# ProProject__CW32__2024-01-24.net
KiCad netlist of a schematic drawn in EasyEDA Pro
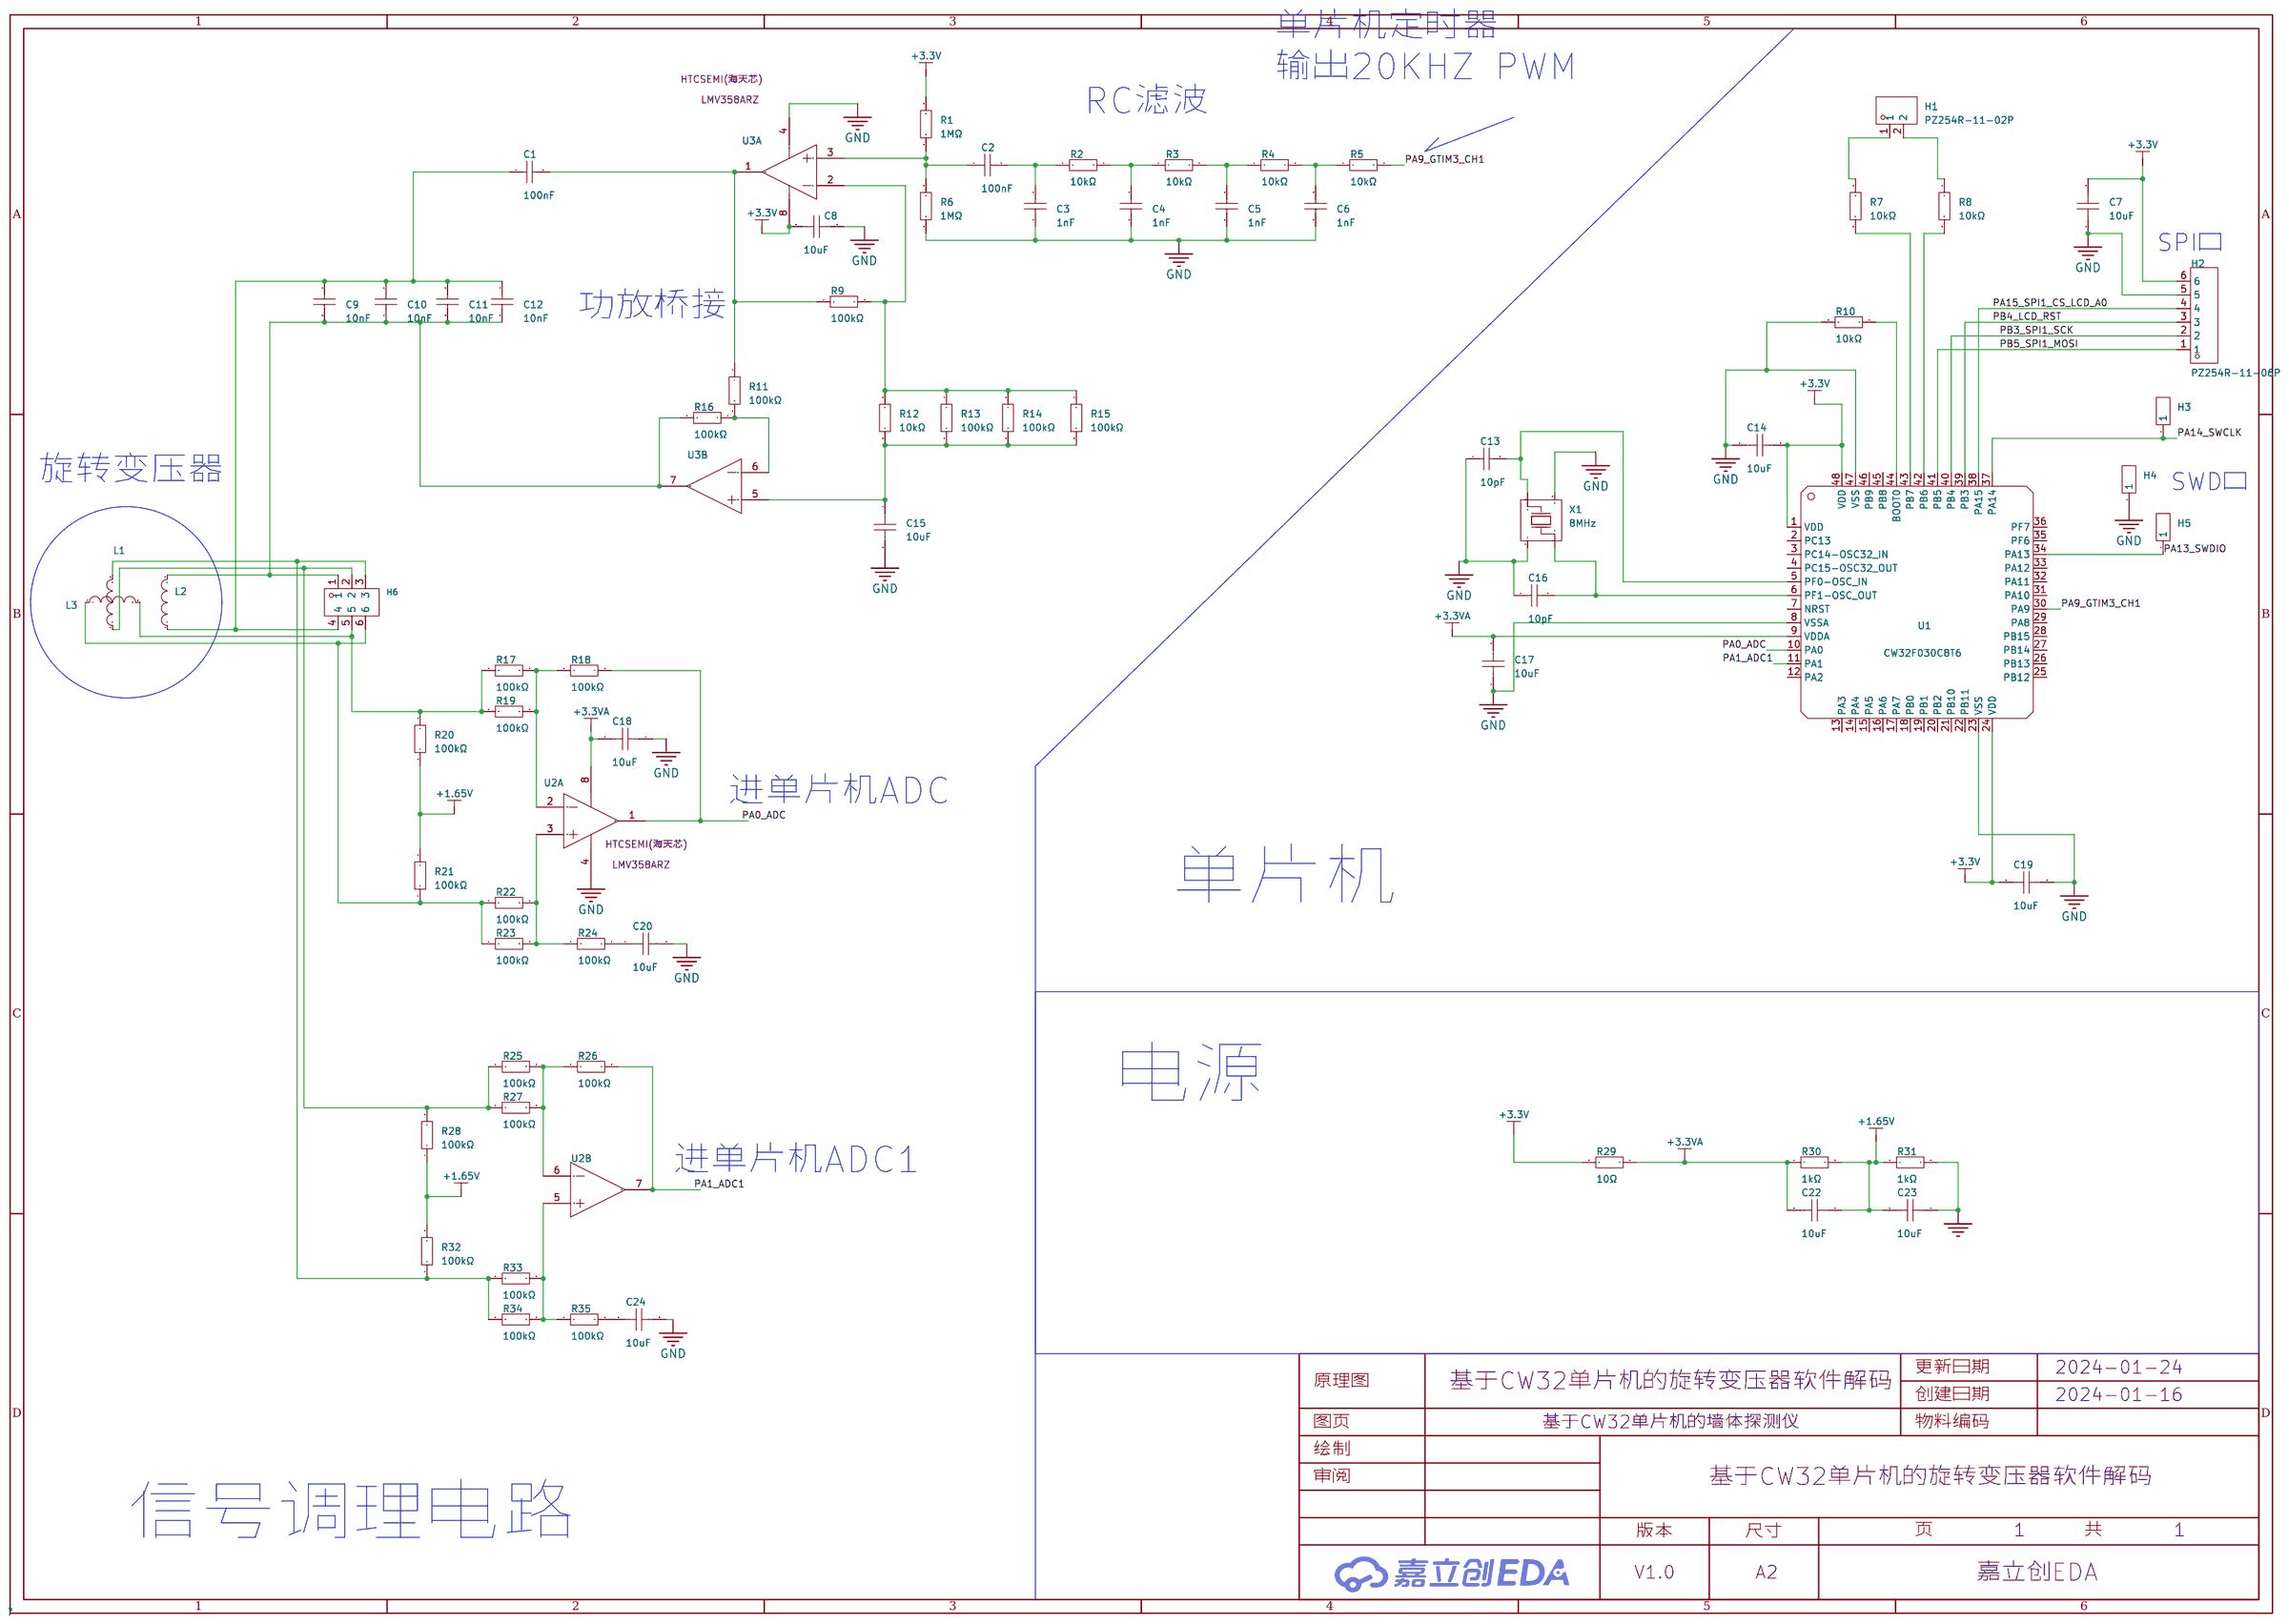
[diagram p0: schematic sheet]

(export (version "E")
  (design (tool "Eeschema 10.0.6"))
  (components
    (comp (ref "C1")
      (value "100nF")
      (footprint "easyedapro:C0603")
      (description "容值:100nF;精度:±10%;额定电压:50V;材质(温度系数):X7R;")
      (fields (field (name "Manufacturer Part") "0603B104K500NT") (field (name "Manufacturer") "FH(风华)"))
      (libsource (lib "easyedapro") (part "0603B104K500NT"))
    )
    (comp (ref "C2")
      (value "100nF")
      (footprint "easyedapro:C0603")
      (description "容值:100nF;精度:±10%;额定电压:50V;材质(温度系数):X7R;")
      (fields (field (name "Manufacturer Part") "0603B104K500NT") (field (name "Manufacturer") "FH(风华)"))
      (libsource (lib "easyedapro") (part "0603B104K500NT"))
    )
    (comp (ref "C3")
      (value "1nF")
      (footprint "easyedapro:C0603")
      (description "容值:1nF;精度:±5%;额定电压:50V;材质(温度系数):NP0;")
      (fields
        (field (name "Manufacturer Part") "CC0603JRNPO9BN102")
        (field (name "Manufacturer") "YAGEO(国巨)")
      )
      (libsource (lib "easyedapro") (part "CC0603JRNPO9BN102"))
    )
    (comp (ref "C4")
      (value "1nF")
      (footprint "easyedapro:C0603")
      (description "容值:1nF;精度:±5%;额定电压:50V;材质(温度系数):NP0;")
      (fields
        (field (name "Manufacturer Part") "CC0603JRNPO9BN102")
        (field (name "Manufacturer") "YAGEO(国巨)")
      )
      (libsource (lib "easyedapro") (part "CC0603JRNPO9BN102"))
    )
    (comp (ref "C5")
      (value "1nF")
      (footprint "easyedapro:C0603")
      (description "容值:1nF;精度:±5%;额定电压:50V;材质(温度系数):NP0;")
      (fields
        (field (name "Manufacturer Part") "CC0603JRNPO9BN102")
        (field (name "Manufacturer") "YAGEO(国巨)")
      )
      (libsource (lib "easyedapro") (part "CC0603JRNPO9BN102"))
    )
    (comp (ref "C6")
      (value "1nF")
      (footprint "easyedapro:C0603")
      (description "容值:1nF;精度:±5%;额定电压:50V;材质(温度系数):NP0;")
      (fields
        (field (name "Manufacturer Part") "CC0603JRNPO9BN102")
        (field (name "Manufacturer") "YAGEO(国巨)")
      )
      (libsource (lib "easyedapro") (part "CC0603JRNPO9BN102"))
    )
    (comp (ref "C7")
      (value "10uF")
      (footprint "easyedapro:C0603")
      (description "容值:10uF;精度:±10%;额定电压:10V;材质(温度系数):X5R;")
      (fields
        (field (name "Manufacturer Part") "CL10A106KP8NNNC")
        (field (name "Manufacturer") "SAMSUNG(三星)")
      )
      (libsource (lib "easyedapro") (part "CL10A106KP8NNNC"))
    )
    (comp (ref "C8")
      (value "10uF")
      (footprint "easyedapro:C0603")
      (description "容值:10uF;精度:±10%;额定电压:10V;材质(温度系数):X5R;")
      (fields
        (field (name "Manufacturer Part") "CL10A106KP8NNNC")
        (field (name "Manufacturer") "SAMSUNG(三星)")
      )
      (libsource (lib "easyedapro") (part "CL10A106KP8NNNC"))
    )
    (comp (ref "C9")
      (value "10nF")
      (footprint "easyedapro:C0603")
      (description "容值:10nF;精度:±10%;额定电压:50V;材质(温度系数):X7R;")
      (fields
        (field (name "Manufacturer Part") "CC0603KRX7R9BB103")
        (field (name "Manufacturer") "YAGEO(国巨)")
      )
      (libsource (lib "easyedapro") (part "CC0603KRX7R9BB103"))
    )
    (comp (ref "C10")
      (value "10nF")
      (footprint "easyedapro:C0603")
      (description "容值:10nF;精度:±10%;额定电压:50V;材质(温度系数):X7R;")
      (fields
        (field (name "Manufacturer Part") "CC0603KRX7R9BB103")
        (field (name "Manufacturer") "YAGEO(国巨)")
      )
      (libsource (lib "easyedapro") (part "CC0603KRX7R9BB103"))
    )
    (comp (ref "C11")
      (value "10nF")
      (footprint "easyedapro:C0603")
      (description "容值:10nF;精度:±10%;额定电压:50V;材质(温度系数):X7R;")
      (fields
        (field (name "Manufacturer Part") "CC0603KRX7R9BB103")
        (field (name "Manufacturer") "YAGEO(国巨)")
      )
      (libsource (lib "easyedapro") (part "CC0603KRX7R9BB103"))
    )
    (comp (ref "C12")
      (value "10nF")
      (footprint "easyedapro:C0603")
      (description "容值:10nF;精度:±10%;额定电压:50V;材质(温度系数):X7R;")
      (fields
        (field (name "Manufacturer Part") "CC0603KRX7R9BB103")
        (field (name "Manufacturer") "YAGEO(国巨)")
      )
      (libsource (lib "easyedapro") (part "CC0603KRX7R9BB103"))
    )
    (comp (ref "C13")
      (value "10pF")
      (footprint "easyedapro:C0603")
      (description "容值:10pF;精度:±5%;额定电压:50V;材质(温度系数):NP0;")
      (fields
        (field (name "Manufacturer Part") "CC0603JRNPO9BN100")
        (field (name "Manufacturer") "YAGEO(国巨)")
      )
      (libsource (lib "easyedapro") (part "CC0603JRNPO9BN100"))
    )
    (comp (ref "C14")
      (value "10uF")
      (footprint "easyedapro:C0603")
      (description "容值:10uF;精度:±10%;额定电压:10V;材质(温度系数):X5R;")
      (fields
        (field (name "Manufacturer Part") "CL10A106KP8NNNC")
        (field (name "Manufacturer") "SAMSUNG(三星)")
      )
      (libsource (lib "easyedapro") (part "CL10A106KP8NNNC"))
    )
    (comp (ref "C15")
      (value "10uF")
      (footprint "easyedapro:C0603")
      (description "容值:10uF;精度:±10%;额定电压:10V;材质(温度系数):X5R;")
      (fields
        (field (name "Manufacturer Part") "CL10A106KP8NNNC")
        (field (name "Manufacturer") "SAMSUNG(三星)")
      )
      (libsource (lib "easyedapro") (part "CL10A106KP8NNNC"))
    )
    (comp (ref "C16")
      (value "10pF")
      (footprint "easyedapro:C0603")
      (description "容值:10pF;精度:±5%;额定电压:50V;材质(温度系数):NP0;")
      (fields
        (field (name "Manufacturer Part") "CC0603JRNPO9BN100")
        (field (name "Manufacturer") "YAGEO(国巨)")
      )
      (libsource (lib "easyedapro") (part "CC0603JRNPO9BN100"))
    )
    (comp (ref "C17")
      (value "10uF")
      (footprint "easyedapro:C0603")
      (description "容值:10uF;精度:±10%;额定电压:10V;材质(温度系数):X5R;")
      (fields
        (field (name "Manufacturer Part") "CL10A106KP8NNNC")
        (field (name "Manufacturer") "SAMSUNG(三星)")
      )
      (libsource (lib "easyedapro") (part "CL10A106KP8NNNC"))
    )
    (comp (ref "C18")
      (value "10uF")
      (footprint "easyedapro:C0603")
      (description "容值:10uF;精度:±10%;额定电压:10V;材质(温度系数):X5R;")
      (fields
        (field (name "Manufacturer Part") "CL10A106KP8NNNC")
        (field (name "Manufacturer") "SAMSUNG(三星)")
      )
      (libsource (lib "easyedapro") (part "CL10A106KP8NNNC"))
    )
    (comp (ref "C19")
      (value "10uF")
      (footprint "easyedapro:C0603")
      (description "容值:10uF;精度:±10%;额定电压:10V;材质(温度系数):X5R;")
      (fields
        (field (name "Manufacturer Part") "CL10A106KP8NNNC")
        (field (name "Manufacturer") "SAMSUNG(三星)")
      )
      (libsource (lib "easyedapro") (part "CL10A106KP8NNNC"))
    )
    (comp (ref "C20")
      (value "10uF")
      (footprint "easyedapro:C0603")
      (description "容值:10uF;精度:±10%;额定电压:10V;材质(温度系数):X5R;")
      (fields
        (field (name "Manufacturer Part") "CL10A106KP8NNNC")
        (field (name "Manufacturer") "SAMSUNG(三星)")
      )
      (libsource (lib "easyedapro") (part "CL10A106KP8NNNC"))
    )
    (comp (ref "C22")
      (value "10uF")
      (footprint "easyedapro:C0603")
      (description "容值:10uF;精度:±10%;额定电压:10V;材质(温度系数):X5R;")
      (fields
        (field (name "Manufacturer Part") "CL10A106KP8NNNC")
        (field (name "Manufacturer") "SAMSUNG(三星)")
      )
      (libsource (lib "easyedapro") (part "CL10A106KP8NNNC"))
    )
    (comp (ref "C23")
      (value "10uF")
      (footprint "easyedapro:C0603")
      (description "容值:10uF;精度:±10%;额定电压:10V;材质(温度系数):X5R;")
      (fields
        (field (name "Manufacturer Part") "CL10A106KP8NNNC")
        (field (name "Manufacturer") "SAMSUNG(三星)")
      )
      (libsource (lib "easyedapro") (part "CL10A106KP8NNNC"))
    )
    (comp (ref "C24")
      (value "10uF")
      (footprint "easyedapro:C0603")
      (description "容值:10uF;精度:±10%;额定电压:10V;材质(温度系数):X5R;")
      (fields
        (field (name "Manufacturer Part") "CL10A106KP8NNNC")
        (field (name "Manufacturer") "SAMSUNG(三星)")
      )
      (libsource (lib "easyedapro") (part "CL10A106KP8NNNC"))
    )
    (comp (ref "H1")
      (value "PZ254R-11-02P")
      (footprint "easyedapro:HDR-TH_2P-P2.54-H-M-W10.4")
      (fields (field (name "Manufacturer") "XFCN(兴飞)"))
      (libsource (lib "easyedapro") (part "PZ254R-11-02P"))
    )
    (comp (ref "H2")
      (value "PZ254R-11-06P")
      (footprint "easyedapro:HDR-TH_6P-P2.54-H-M-W10.4")
      (fields (field (name "Manufacturer") "XFCN(兴飞)"))
      (libsource (lib "easyedapro") (part "PZ254R-11-06P"))
    )
    (comp (ref "H3")
      (value "~")
      (footprint "easyedapro:HDR-TH_1P-V-M_XKB_X4611WV-01I-C28D40")
      (libsource (lib "easyedapro") (part "HDR_1x1"))
    )
    (comp (ref "H4")
      (value "~")
      (footprint "easyedapro:HDR-TH_1P-V-M_XKB_X4611WV-01I-C28D40")
      (libsource (lib "easyedapro") (part "HDR_1x1"))
    )
    (comp (ref "H5")
      (value "~")
      (footprint "easyedapro:HDR-TH_1P-V-M_XKB_X4611WV-01I-C28D40")
      (libsource (lib "easyedapro") (part "HDR_1x1"))
    )
    (comp (ref "H6")
      (value "PZ254-2-03-Z-8.5")
      (footprint "easyedapro:HDR-TH_6P-P2.54-V-M-R2-C3-S2.54")
      (fields (field (name "Manufacturer") "HCTL(华灿天禄)"))
      (libsource (lib "easyedapro") (part "PZ254-2-03-Z-8.5"))
    )
    (comp (ref "L1")
      (value "10uH")
      (footprint "easyedapro:L1206")
      (libsource (lib "easyedapro") (part "CMI321609VR27KT"))
    )
    (comp (ref "L2")
      (value "6.3uH")
      (footprint "easyedapro:L1206")
      (libsource (lib "easyedapro") (part "CMI321609VR27KT"))
    )
    (comp (ref "L3")
      (value "10uH")
      (footprint "easyedapro:L1206")
      (libsource (lib "easyedapro") (part "CMI321609VR27KT"))
    )
    (comp (ref "R1")
      (value "1MΩ")
      (footprint "easyedapro:R0603")
      (description "电阻类型:厚膜电阻;阻值:1MΩ;精度:±1%;功率:100mW;")
      (fields
        (field (name "Manufacturer Part") "0603WAF1004T5E")
        (field (name "Manufacturer") "UNI-ROYAL(厚声)")
      )
      (libsource (lib "easyedapro") (part "0603WAF1004T5E"))
    )
    (comp (ref "R2")
      (value "10kΩ")
      (footprint "easyedapro:R0603")
      (description "电阻类型:厚膜电阻;阻值:10kΩ;精度:±1%;功率:100mW;")
      (fields (field (name "Manufacturer Part") "RC0603FR-0710KL") (field (name "Manufacturer") "YAGEO(国巨)"))
      (libsource (lib "easyedapro") (part "RC0603FR-0710KL"))
    )
    (comp (ref "R3")
      (value "10kΩ")
      (footprint "easyedapro:R0603")
      (description "电阻类型:厚膜电阻;阻值:10kΩ;精度:±1%;功率:100mW;")
      (fields (field (name "Manufacturer Part") "RC0603FR-0710KL") (field (name "Manufacturer") "YAGEO(国巨)"))
      (libsource (lib "easyedapro") (part "RC0603FR-0710KL"))
    )
    (comp (ref "R4")
      (value "10kΩ")
      (footprint "easyedapro:R0603")
      (description "电阻类型:厚膜电阻;阻值:10kΩ;精度:±1%;功率:100mW;")
      (fields (field (name "Manufacturer Part") "RC0603FR-0710KL") (field (name "Manufacturer") "YAGEO(国巨)"))
      (libsource (lib "easyedapro") (part "RC0603FR-0710KL"))
    )
    (comp (ref "R5")
      (value "10kΩ")
      (footprint "easyedapro:R0603")
      (description "电阻类型:厚膜电阻;阻值:10kΩ;精度:±1%;功率:100mW;")
      (fields (field (name "Manufacturer Part") "RC0603FR-0710KL") (field (name "Manufacturer") "YAGEO(国巨)"))
      (libsource (lib "easyedapro") (part "RC0603FR-0710KL"))
    )
    (comp (ref "R6")
      (value "1MΩ")
      (footprint "easyedapro:R0603")
      (description "电阻类型:厚膜电阻;阻值:1MΩ;精度:±1%;功率:100mW;")
      (fields
        (field (name "Manufacturer Part") "0603WAF1004T5E")
        (field (name "Manufacturer") "UNI-ROYAL(厚声)")
      )
      (libsource (lib "easyedapro") (part "0603WAF1004T5E"))
    )
    (comp (ref "R7")
      (value "10kΩ")
      (footprint "easyedapro:R0603")
      (description "电阻类型:厚膜电阻;阻值:10kΩ;精度:±1%;功率:100mW;")
      (fields (field (name "Manufacturer Part") "RC0603FR-0710KL") (field (name "Manufacturer") "YAGEO(国巨)"))
      (libsource (lib "easyedapro") (part "RC0603FR-0710KL"))
    )
    (comp (ref "R8")
      (value "10kΩ")
      (footprint "easyedapro:R0603")
      (description "电阻类型:厚膜电阻;阻值:10kΩ;精度:±1%;功率:100mW;")
      (fields (field (name "Manufacturer Part") "RC0603FR-0710KL") (field (name "Manufacturer") "YAGEO(国巨)"))
      (libsource (lib "easyedapro") (part "RC0603FR-0710KL"))
    )
    (comp (ref "R9")
      (value "100kΩ")
      (footprint "easyedapro:R0603")
      (description "电阻类型:厚膜电阻;阻值:100kΩ;精度:±1%;功率:100mW;")
      (fields (field (name "Manufacturer Part") "RC0603FR-07100KL") (field (name "Manufacturer") "YAGEO(国巨)"))
      (libsource (lib "easyedapro") (part "RC0603FR-07100KL"))
    )
    (comp (ref "R10")
      (value "10kΩ")
      (footprint "easyedapro:R0603")
      (description "电阻类型:厚膜电阻;阻值:10kΩ;精度:±1%;功率:100mW;")
      (fields (field (name "Manufacturer Part") "RC0603FR-0710KL") (field (name "Manufacturer") "YAGEO(国巨)"))
      (libsource (lib "easyedapro") (part "RC0603FR-0710KL"))
    )
    (comp (ref "R11")
      (value "100kΩ")
      (footprint "easyedapro:R0603")
      (description "电阻类型:厚膜电阻;阻值:100kΩ;精度:±1%;功率:100mW;")
      (fields (field (name "Manufacturer Part") "RC0603FR-07100KL") (field (name "Manufacturer") "YAGEO(国巨)"))
      (libsource (lib "easyedapro") (part "RC0603FR-07100KL"))
    )
    (comp (ref "R12")
      (value "10kΩ")
      (footprint "easyedapro:R0603")
      (description "电阻类型:厚膜电阻;阻值:10kΩ;精度:±1%;功率:100mW;")
      (fields (field (name "Manufacturer Part") "RC0603FR-0710KL") (field (name "Manufacturer") "YAGEO(国巨)"))
      (libsource (lib "easyedapro") (part "RC0603FR-0710KL"))
    )
    (comp (ref "R13")
      (value "100kΩ")
      (footprint "easyedapro:R0603")
      (description "电阻类型:厚膜电阻;阻值:100kΩ;精度:±1%;功率:100mW;")
      (fields (field (name "Manufacturer Part") "RC0603FR-07100KL") (field (name "Manufacturer") "YAGEO(国巨)"))
      (libsource (lib "easyedapro") (part "RC0603FR-07100KL"))
    )
    (comp (ref "R14")
      (value "100kΩ")
      (footprint "easyedapro:R0603")
      (description "电阻类型:厚膜电阻;阻值:100kΩ;精度:±1%;功率:100mW;")
      (fields (field (name "Manufacturer Part") "RC0603FR-07100KL") (field (name "Manufacturer") "YAGEO(国巨)"))
      (libsource (lib "easyedapro") (part "RC0603FR-07100KL"))
    )
    (comp (ref "R15")
      (value "100kΩ")
      (footprint "easyedapro:R0603")
      (description "电阻类型:厚膜电阻;阻值:100kΩ;精度:±1%;功率:100mW;")
      (fields (field (name "Manufacturer Part") "RC0603FR-07100KL") (field (name "Manufacturer") "YAGEO(国巨)"))
      (libsource (lib "easyedapro") (part "RC0603FR-07100KL"))
    )
    (comp (ref "R16")
      (value "100kΩ")
      (footprint "easyedapro:R0603")
      (description "电阻类型:厚膜电阻;阻值:100kΩ;精度:±1%;功率:100mW;")
      (fields (field (name "Manufacturer Part") "RC0603FR-07100KL") (field (name "Manufacturer") "YAGEO(国巨)"))
      (libsource (lib "easyedapro") (part "RC0603FR-07100KL"))
    )
    (comp (ref "R17")
      (value "100kΩ")
      (footprint "easyedapro:R0603")
      (description "电阻类型:厚膜电阻;阻值:100kΩ;精度:±1%;功率:100mW;")
      (fields (field (name "Manufacturer Part") "RC0603FR-07100KL") (field (name "Manufacturer") "YAGEO(国巨)"))
      (libsource (lib "easyedapro") (part "RC0603FR-07100KL"))
    )
    (comp (ref "R18")
      (value "100kΩ")
      (footprint "easyedapro:R0603")
      (description "电阻类型:厚膜电阻;阻值:100kΩ;精度:±1%;功率:100mW;")
      (fields (field (name "Manufacturer Part") "RC0603FR-07100KL") (field (name "Manufacturer") "YAGEO(国巨)"))
      (libsource (lib "easyedapro") (part "RC0603FR-07100KL"))
    )
    (comp (ref "R19")
      (value "100kΩ")
      (footprint "easyedapro:R0603")
      (description "电阻类型:厚膜电阻;阻值:100kΩ;精度:±1%;功率:100mW;")
      (fields (field (name "Manufacturer Part") "RC0603FR-07100KL") (field (name "Manufacturer") "YAGEO(国巨)"))
      (libsource (lib "easyedapro") (part "RC0603FR-07100KL"))
    )
    (comp (ref "R20")
      (value "100kΩ")
      (footprint "easyedapro:R0603")
      (description "电阻类型:厚膜电阻;阻值:100kΩ;精度:±1%;功率:100mW;")
      (fields (field (name "Manufacturer Part") "RC0603FR-07100KL") (field (name "Manufacturer") "YAGEO(国巨)"))
      (libsource (lib "easyedapro") (part "RC0603FR-07100KL"))
    )
    (comp (ref "R21")
      (value "100kΩ")
      (footprint "easyedapro:R0603")
      (description "电阻类型:厚膜电阻;阻值:100kΩ;精度:±1%;功率:100mW;")
      (fields (field (name "Manufacturer Part") "RC0603FR-07100KL") (field (name "Manufacturer") "YAGEO(国巨)"))
      (libsource (lib "easyedapro") (part "RC0603FR-07100KL"))
    )
    (comp (ref "R22")
      (value "100kΩ")
      (footprint "easyedapro:R0603")
      (description "电阻类型:厚膜电阻;阻值:100kΩ;精度:±1%;功率:100mW;")
      (fields (field (name "Manufacturer Part") "RC0603FR-07100KL") (field (name "Manufacturer") "YAGEO(国巨)"))
      (libsource (lib "easyedapro") (part "RC0603FR-07100KL"))
    )
    (comp (ref "R23")
      (value "100kΩ")
      (footprint "easyedapro:R0603")
      (description "电阻类型:厚膜电阻;阻值:100kΩ;精度:±1%;功率:100mW;")
      (fields (field (name "Manufacturer Part") "RC0603FR-07100KL") (field (name "Manufacturer") "YAGEO(国巨)"))
      (libsource (lib "easyedapro") (part "RC0603FR-07100KL"))
    )
    (comp (ref "R24")
      (value "100kΩ")
      (footprint "easyedapro:R0603")
      (description "电阻类型:厚膜电阻;阻值:100kΩ;精度:±1%;功率:100mW;")
      (fields (field (name "Manufacturer Part") "RC0603FR-07100KL") (field (name "Manufacturer") "YAGEO(国巨)"))
      (libsource (lib "easyedapro") (part "RC0603FR-07100KL"))
    )
    (comp (ref "R25")
      (value "100kΩ")
      (footprint "easyedapro:R0603")
      (description "电阻类型:厚膜电阻;阻值:100kΩ;精度:±1%;功率:100mW;")
      (fields (field (name "Manufacturer Part") "RC0603FR-07100KL") (field (name "Manufacturer") "YAGEO(国巨)"))
      (libsource (lib "easyedapro") (part "RC0603FR-07100KL"))
    )
    (comp (ref "R26")
      (value "100kΩ")
      (footprint "easyedapro:R0603")
      (description "电阻类型:厚膜电阻;阻值:100kΩ;精度:±1%;功率:100mW;")
      (fields (field (name "Manufacturer Part") "RC0603FR-07100KL") (field (name "Manufacturer") "YAGEO(国巨)"))
      (libsource (lib "easyedapro") (part "RC0603FR-07100KL"))
    )
    (comp (ref "R27")
      (value "100kΩ")
      (footprint "easyedapro:R0603")
      (description "电阻类型:厚膜电阻;阻值:100kΩ;精度:±1%;功率:100mW;")
      (fields (field (name "Manufacturer Part") "RC0603FR-07100KL") (field (name "Manufacturer") "YAGEO(国巨)"))
      (libsource (lib "easyedapro") (part "RC0603FR-07100KL"))
    )
    (comp (ref "R28")
      (value "100kΩ")
      (footprint "easyedapro:R0603")
      (description "电阻类型:厚膜电阻;阻值:100kΩ;精度:±1%;功率:100mW;")
      (fields (field (name "Manufacturer Part") "RC0603FR-07100KL") (field (name "Manufacturer") "YAGEO(国巨)"))
      (libsource (lib "easyedapro") (part "RC0603FR-07100KL"))
    )
    (comp (ref "R29")
      (value "10Ω")
      (footprint "easyedapro:R0603")
      (description "电阻类型:厚膜电阻;阻值:10Ω;精度:±1%;功率:100mW;")
      (fields
        (field (name "Manufacturer Part") "0603WAF100JT5E")
        (field (name "Manufacturer") "UNI-ROYAL(厚声)")
      )
      (libsource (lib "easyedapro") (part "0603WAF100JT5E"))
    )
    (comp (ref "R30")
      (value "1kΩ")
      (footprint "easyedapro:R0603")
      (description "电阻类型:厚膜电阻;阻值:1kΩ;精度:±1%;功率:100mW;")
      (fields (field (name "Manufacturer Part") "RC0603FR-071KL") (field (name "Manufacturer") "YAGEO(国巨)"))
      (libsource (lib "easyedapro") (part "RC0603FR-071KL"))
    )
    (comp (ref "R31")
      (value "1kΩ")
      (footprint "easyedapro:R0603")
      (description "电阻类型:厚膜电阻;阻值:1kΩ;精度:±1%;功率:100mW;")
      (fields (field (name "Manufacturer Part") "RC0603FR-071KL") (field (name "Manufacturer") "YAGEO(国巨)"))
      (libsource (lib "easyedapro") (part "RC0603FR-071KL"))
    )
    (comp (ref "R32")
      (value "100kΩ")
      (footprint "easyedapro:R0603")
      (description "电阻类型:厚膜电阻;阻值:100kΩ;精度:±1%;功率:100mW;")
      (fields (field (name "Manufacturer Part") "RC0603FR-07100KL") (field (name "Manufacturer") "YAGEO(国巨)"))
      (libsource (lib "easyedapro") (part "RC0603FR-07100KL"))
    )
    (comp (ref "R33")
      (value "100kΩ")
      (footprint "easyedapro:R0603")
      (description "电阻类型:厚膜电阻;阻值:100kΩ;精度:±1%;功率:100mW;")
      (fields (field (name "Manufacturer Part") "RC0603FR-07100KL") (field (name "Manufacturer") "YAGEO(国巨)"))
      (libsource (lib "easyedapro") (part "RC0603FR-07100KL"))
    )
    (comp (ref "R34")
      (value "100kΩ")
      (footprint "easyedapro:R0603")
      (description "电阻类型:厚膜电阻;阻值:100kΩ;精度:±1%;功率:100mW;")
      (fields (field (name "Manufacturer Part") "RC0603FR-07100KL") (field (name "Manufacturer") "YAGEO(国巨)"))
      (libsource (lib "easyedapro") (part "RC0603FR-07100KL"))
    )
    (comp (ref "R35")
      (value "100kΩ")
      (footprint "easyedapro:R0603")
      (description "电阻类型:厚膜电阻;阻值:100kΩ;精度:±1%;功率:100mW;")
      (fields (field (name "Manufacturer Part") "RC0603FR-07100KL") (field (name "Manufacturer") "YAGEO(国巨)"))
      (libsource (lib "easyedapro") (part "RC0603FR-07100KL"))
    )
    (comp (ref "U1")
      (value "CW32F030C8T6")
      (footprint "easyedapro:LQFP-48_L7.0-W7.0-P0.50-LS9.0-TL")
      (fields (field (name "Manufacturer") "CW(芯源)"))
      (libsource (lib "easyedapro") (part "CW32F030C8T6_C3019113"))
    )
    (comp (ref "U2")
      (value "{ManufacturerPart!}")
      (footprint "easyedapro:SOP-8_L4.9-W3.9-P1.27-LS6.0-BL")
      (description "CMOS低功耗双路运算放大器")
      (fields (field (name "Manufacturer Part") "LMV358ARZ") (field (name "Manufacturer") "HTCSEMI(海天芯)"))
      (libsource (lib "easyedapro") (part "LMV358ARZ"))
    )
    (comp (ref "U3")
      (value "{ManufacturerPart!}")
      (footprint "easyedapro:SOP-8_L4.9-W3.9-P1.27-LS6.0-BL")
      (description "CMOS低功耗双路运算放大器")
      (fields (field (name "Manufacturer Part") "LMV358ARZ") (field (name "Manufacturer") "HTCSEMI(海天芯)"))
      (libsource (lib "easyedapro") (part "LMV358ARZ"))
    )
    (comp (ref "X1")
      (value "8MHz")
      (footprint "easyedapro:OSC-SMD_4P-L3.2-W2.5-BL")
      (description "频率:8MHz;负载电容:10pF;频率公差:±10ppm;")
      (fields (field (name "Manufacturer Part") "TAXM8M4RDBCCT2T") (field (name "Manufacturer") "YJX(雅晶鑫)"))
      (libsource (lib "easyedapro") (part "TAXM8M4RDBCCT2T"))
    )
  )
  (nets
    (net (code "1") (name "+1.65V") (class "Default")
      (node (ref "C22") (pin "1") (pinfunction "1_1") (pintype "unspecified"))
      (node (ref "C23") (pin "2") (pinfunction "2_2") (pintype "unspecified"))
      (node (ref "R20") (pin "1") (pinfunction "1_1") (pintype "unspecified"))
      (node (ref "R21") (pin "2") (pinfunction "2_2") (pintype "unspecified"))
      (node (ref "R28") (pin "1") (pinfunction "1_1") (pintype "unspecified"))
      (node (ref "R30") (pin "2") (pinfunction "2_2") (pintype "input"))
      (node (ref "R31") (pin "1") (pinfunction "1_1") (pintype "input"))
      (node (ref "R32") (pin "2") (pinfunction "2_2") (pintype "unspecified"))
    )
    (net (code "2") (name "+3.3V") (class "Default")
      (node (ref "C14") (pin "2") (pinfunction "2_2") (pintype "unspecified"))
      (node (ref "C19") (pin "1") (pinfunction "1_1") (pintype "unspecified"))
      (node (ref "C7") (pin "2") (pinfunction "2_2") (pintype "unspecified"))
      (node (ref "C8") (pin "2") (pinfunction "2_2") (pintype "unspecified"))
      (node (ref "H2") (pin "6") (pinfunction "6_6") (pintype "unspecified"))
      (node (ref "R1") (pin "2") (pinfunction "2_2") (pintype "input"))
      (node (ref "R29") (pin "2") (pinfunction "2_2") (pintype "input"))
      (node (ref "U1") (pin "1") (pinfunction "VDD_1") (pintype "input"))
      (node (ref "U1") (pin "24") (pinfunction "VDD_24") (pintype "input"))
      (node (ref "U1") (pin "48") (pinfunction "VDD_48") (pintype "input"))
      (node (ref "U3") (pin "8") (pinfunction "VCC_8") (pintype "input"))
    )
    (net (code "3") (name "+3.3VA") (class "Default")
      (node (ref "C17") (pin "2") (pinfunction "2_2") (pintype "unspecified"))
      (node (ref "C18") (pin "2") (pinfunction "2_2") (pintype "unspecified"))
      (node (ref "C22") (pin "2") (pinfunction "2_2") (pintype "unspecified"))
      (node (ref "R29") (pin "1") (pinfunction "1_1") (pintype "input"))
      (node (ref "R30") (pin "1") (pinfunction "1_1") (pintype "input"))
      (node (ref "U1") (pin "9") (pinfunction "VDDA_9") (pintype "input"))
      (node (ref "U2") (pin "8") (pinfunction "VCC_8") (pintype "input"))
    )
    (net (code "4") (name "/PA0_ADC") (class "Default")
      (node (ref "R18") (pin "2") (pinfunction "2_2") (pintype "unspecified"))
      (node (ref "U1") (pin "10") (pinfunction "PA0_10") (pintype "input"))
      (node (ref "U2") (pin "1") (pinfunction "OUT_1") (pintype "output"))
    )
    (net (code "5") (name "/PA1_ADC1") (class "Default")
      (node (ref "R26") (pin "2") (pinfunction "2_2") (pintype "unspecified"))
      (node (ref "U1") (pin "11") (pinfunction "PA1_11") (pintype "input"))
      (node (ref "U2") (pin "7") (pinfunction "OUT2_7") (pintype "output"))
    )
    (net (code "6") (name "/PA9_GTIM3_CH1") (class "Default")
      (node (ref "R5") (pin "2") (pinfunction "2_2") (pintype "input"))
      (node (ref "U1") (pin "30") (pinfunction "PA9_30") (pintype "input"))
    )
    (net (code "7") (name "/PA13_SWDIO") (class "Default")
      (node (ref "H5") (pin "1") (pinfunction "1_1") (pintype "unspecified"))
      (node (ref "U1") (pin "34") (pinfunction "PA13_34") (pintype "input"))
    )
    (net (code "8") (name "/PA14_SWCLK") (class "Default")
      (node (ref "H3") (pin "1") (pinfunction "1_1") (pintype "unspecified"))
      (node (ref "U1") (pin "37") (pinfunction "PA14_37") (pintype "input"))
    )
    (net (code "9") (name "/PA15_SPI1_CS_LCD_A0") (class "Default")
      (node (ref "H2") (pin "4") (pinfunction "4_4") (pintype "unspecified"))
      (node (ref "U1") (pin "38") (pinfunction "PA15_38") (pintype "input"))
    )
    (net (code "10") (name "/PB3_SPI1_SCK") (class "Default")
      (node (ref "H2") (pin "2") (pinfunction "2_2") (pintype "unspecified"))
      (node (ref "U1") (pin "40") (pinfunction "PB4_40") (pintype "input"))
    )
    (net (code "11") (name "/PB4_LCD_RST") (class "Default")
      (node (ref "H2") (pin "3") (pinfunction "3_3") (pintype "unspecified"))
      (node (ref "U1") (pin "39") (pinfunction "PB3_39") (pintype "input"))
    )
    (net (code "12") (name "/PB5_SPI1_MOSI") (class "Default")
      (node (ref "H2") (pin "1") (pinfunction "1_1") (pintype "unspecified"))
      (node (ref "U1") (pin "41") (pinfunction "PB5_41") (pintype "input"))
    )
    (net (code "13") (name "GND") (class "Default")
      (node (ref "C13") (pin "1") (pinfunction "1_1") (pintype "input"))
      (node (ref "C14") (pin "1") (pinfunction "1_1") (pintype "unspecified"))
      (node (ref "C15") (pin "2") (pinfunction "2_2") (pintype "unspecified"))
      (node (ref "C16") (pin "1") (pinfunction "1_1") (pintype "input"))
      (node (ref "C17") (pin "1") (pinfunction "1_1") (pintype "unspecified"))
      (node (ref "C18") (pin "1") (pinfunction "1_1") (pintype "unspecified"))
      (node (ref "C19") (pin "2") (pinfunction "2_2") (pintype "unspecified"))
      (node (ref "C20") (pin "2") (pinfunction "2_2") (pintype "unspecified"))
      (node (ref "C23") (pin "1") (pinfunction "1_1") (pintype "unspecified"))
      (node (ref "C24") (pin "2") (pinfunction "2_2") (pintype "unspecified"))
      (node (ref "C3") (pin "1") (pinfunction "1_1") (pintype "input"))
      (node (ref "C4") (pin "1") (pinfunction "1_1") (pintype "input"))
      (node (ref "C5") (pin "1") (pinfunction "1_1") (pintype "input"))
      (node (ref "C6") (pin "1") (pinfunction "1_1") (pintype "input"))
      (node (ref "C7") (pin "1") (pinfunction "1_1") (pintype "unspecified"))
      (node (ref "C8") (pin "1") (pinfunction "1_1") (pintype "unspecified"))
      (node (ref "H2") (pin "5") (pinfunction "5_5") (pintype "unspecified"))
      (node (ref "H4") (pin "1") (pinfunction "1_1") (pintype "unspecified"))
      (node (ref "R10") (pin "2") (pinfunction "2_2") (pintype "input"))
      (node (ref "R31") (pin "2") (pinfunction "2_2") (pintype "input"))
      (node (ref "R6") (pin "1") (pinfunction "1_1") (pintype "input"))
      (node (ref "U1") (pin "23") (pinfunction "VSS_23") (pintype "input"))
      (node (ref "U1") (pin "47") (pinfunction "VSS_47") (pintype "input"))
      (node (ref "U1") (pin "8") (pinfunction "VSSA_8") (pintype "input"))
      (node (ref "U2") (pin "4") (pinfunction "GND_4") (pintype "input"))
      (node (ref "U3") (pin "4") (pinfunction "GND_4") (pintype "input"))
      (node (ref "X1") (pin "2") (pinfunction "2_2") (pintype "input"))
      (node (ref "X1") (pin "4") (pinfunction "4_4") (pintype "input"))
    )
    (net (code "14") (name "Net-(C1-Pad1)") (class "Default")
      (node (ref "C1") (pin "1") (pinfunction "1_1") (pintype "input"))
      (node (ref "C10") (pin "2") (pinfunction "2_2") (pintype "input"))
      (node (ref "C11") (pin "2") (pinfunction "2_2") (pintype "input"))
      (node (ref "C12") (pin "2") (pinfunction "2_2") (pintype "input"))
      (node (ref "C9") (pin "2") (pinfunction "2_2") (pintype "input"))
      (node (ref "H6") (pin "4") (pinfunction "4_4") (pintype "input"))
      (node (ref "L2") (pin "1") (pinfunction "1_1") (pintype "input"))
    )
    (net (code "15") (name "Net-(C2-Pad2)") (class "Default")
      (node (ref "C2") (pin "2") (pinfunction "2_2") (pintype "input"))
      (node (ref "C3") (pin "2") (pinfunction "2_2") (pintype "input"))
      (node (ref "R2") (pin "1") (pinfunction "1_1") (pintype "input"))
    )
    (net (code "16") (name "Net-(C4-Pad2)") (class "Default")
      (node (ref "C4") (pin "2") (pinfunction "2_2") (pintype "input"))
      (node (ref "R2") (pin "2") (pinfunction "2_2") (pintype "input"))
      (node (ref "R3") (pin "1") (pinfunction "1_1") (pintype "input"))
    )
    (net (code "17") (name "Net-(C5-Pad2)") (class "Default")
      (node (ref "C5") (pin "2") (pinfunction "2_2") (pintype "input"))
      (node (ref "R3") (pin "2") (pinfunction "2_2") (pintype "input"))
      (node (ref "R4") (pin "1") (pinfunction "1_1") (pintype "input"))
    )
    (net (code "18") (name "Net-(C6-Pad2)") (class "Default")
      (node (ref "C6") (pin "2") (pinfunction "2_2") (pintype "input"))
      (node (ref "R4") (pin "2") (pinfunction "2_2") (pintype "input"))
      (node (ref "R5") (pin "1") (pinfunction "1_1") (pintype "input"))
    )
    (net (code "19") (name "Net-(C20-Pad1)") (class "Default")
      (node (ref "C20") (pin "1") (pinfunction "1_1") (pintype "unspecified"))
      (node (ref "R24") (pin "2") (pinfunction "2_2") (pintype "unspecified"))
    )
    (net (code "20") (name "Net-(C24-Pad1)") (class "Default")
      (node (ref "C24") (pin "1") (pinfunction "1_1") (pintype "unspecified"))
      (node (ref "R35") (pin "2") (pinfunction "2_2") (pintype "unspecified"))
    )
    (net (code "21") (name "Net-(H1-Pad1)") (class "Default")
      (node (ref "H1") (pin "1") (pinfunction "1_1") (pintype "unspecified"))
      (node (ref "R7") (pin "1") (pinfunction "1_1") (pintype "input"))
    )
    (net (code "22") (name "Net-(H1-Pad2)") (class "Default")
      (node (ref "H1") (pin "2") (pinfunction "2_2") (pintype "unspecified"))
      (node (ref "R8") (pin "1") (pinfunction "1_1") (pintype "input"))
    )
    (net (code "23") (name "Net-(H6-Pad2)") (class "Default")
      (node (ref "H6") (pin "2") (pinfunction "2_2") (pintype "input"))
      (node (ref "L1") (pin "1") (pinfunction "1_1") (pintype "input"))
      (node (ref "R25") (pin "1") (pinfunction "1_1") (pintype "unspecified"))
      (node (ref "R27") (pin "1") (pinfunction "1_1") (pintype "unspecified"))
      (node (ref "R28") (pin "2") (pinfunction "2_2") (pintype "unspecified"))
    )
    (net (code "24") (name "Net-(H6-Pad3)") (class "Default")
      (node (ref "H6") (pin "3") (pinfunction "3_3") (pintype "input"))
      (node (ref "L1") (pin "2") (pinfunction "2_2") (pintype "input"))
      (node (ref "R32") (pin "1") (pinfunction "1_1") (pintype "unspecified"))
      (node (ref "R33") (pin "1") (pinfunction "1_1") (pintype "unspecified"))
      (node (ref "R34") (pin "1") (pinfunction "1_1") (pintype "unspecified"))
    )
    (net (code "25") (name "Net-(H6-Pad5)") (class "Default")
      (node (ref "H6") (pin "5") (pinfunction "5_5") (pintype "input"))
      (node (ref "L3") (pin "2") (pinfunction "2_2") (pintype "input"))
      (node (ref "R17") (pin "1") (pinfunction "1_1") (pintype "unspecified"))
      (node (ref "R19") (pin "1") (pinfunction "1_1") (pintype "unspecified"))
      (node (ref "R20") (pin "2") (pinfunction "2_2") (pintype "unspecified"))
    )
    (net (code "26") (name "Net-(H6-Pad6)") (class "Default")
      (node (ref "H6") (pin "6") (pinfunction "6_6") (pintype "input"))
      (node (ref "L3") (pin "1") (pinfunction "1_1") (pintype "input"))
      (node (ref "R21") (pin "1") (pinfunction "1_1") (pintype "unspecified"))
      (node (ref "R22") (pin "1") (pinfunction "1_1") (pintype "unspecified"))
      (node (ref "R23") (pin "1") (pinfunction "1_1") (pintype "unspecified"))
    )
    (net (code "27") (name "Net-(U1-BOOT0)") (class "Default")
      (node (ref "R10") (pin "1") (pinfunction "1_1") (pintype "input"))
      (node (ref "U1") (pin "44") (pinfunction "BOOT0_44") (pintype "input"))
    )
    (net (code "28") (name "Net-(U1-PB6)") (class "Default")
      (node (ref "R8") (pin "2") (pinfunction "2_2") (pintype "input"))
      (node (ref "U1") (pin "42") (pinfunction "PB6_42") (pintype "input"))
    )
    (net (code "29") (name "Net-(U1-PB7)") (class "Default")
      (node (ref "R7") (pin "2") (pinfunction "2_2") (pintype "input"))
      (node (ref "U1") (pin "43") (pinfunction "PB7_43") (pintype "input"))
    )
    (net (code "30") (name "Net-(U1-PF0-OSC_IN)") (class "Default")
      (node (ref "C13") (pin "2") (pinfunction "2_2") (pintype "input"))
      (node (ref "U1") (pin "5") (pinfunction "PF0-OSC_IN_5") (pintype "input"))
      (node (ref "X1") (pin "3") (pinfunction "3_3") (pintype "input"))
    )
    (net (code "31") (name "Net-(U1-PF1-OSC_OUT)") (class "Default")
      (node (ref "C16") (pin "2") (pinfunction "2_2") (pintype "input"))
      (node (ref "U1") (pin "6") (pinfunction "PF1-OSC_OUT_6") (pintype "input"))
      (node (ref "X1") (pin "1") (pinfunction "1_1") (pintype "input"))
    )
    (net (code "32") (name "Net-(U2A-IN1+)") (class "Default")
      (node (ref "R22") (pin "2") (pinfunction "2_2") (pintype "unspecified"))
      (node (ref "R23") (pin "2") (pinfunction "2_2") (pintype "unspecified"))
      (node (ref "R24") (pin "1") (pinfunction "1_1") (pintype "unspecified"))
      (node (ref "U2") (pin "3") (pinfunction "IN1+_3") (pintype "input"))
    )
    (net (code "33") (name "Net-(U2A-IN1-)") (class "Default")
      (node (ref "R17") (pin "2") (pinfunction "2_2") (pintype "unspecified"))
      (node (ref "R18") (pin "1") (pinfunction "1_1") (pintype "unspecified"))
      (node (ref "R19") (pin "2") (pinfunction "2_2") (pintype "unspecified"))
      (node (ref "U2") (pin "2") (pinfunction "IN1-_2") (pintype "input"))
    )
    (net (code "34") (name "Net-(U2B-IN2+)") (class "Default")
      (node (ref "R33") (pin "2") (pinfunction "2_2") (pintype "unspecified"))
      (node (ref "R34") (pin "2") (pinfunction "2_2") (pintype "unspecified"))
      (node (ref "R35") (pin "1") (pinfunction "1_1") (pintype "unspecified"))
      (node (ref "U2") (pin "5") (pinfunction "IN2+_5") (pintype "input"))
    )
    (net (code "35") (name "Net-(U2B-IN2-)") (class "Default")
      (node (ref "R25") (pin "2") (pinfunction "2_2") (pintype "unspecified"))
      (node (ref "R26") (pin "1") (pinfunction "1_1") (pintype "unspecified"))
      (node (ref "R27") (pin "2") (pinfunction "2_2") (pintype "unspecified"))
      (node (ref "U2") (pin "6") (pinfunction "IN2-_6") (pintype "input"))
    )
    (net (code "36") (name "Net-(U3A-IN1+)") (class "Default")
      (node (ref "C2") (pin "1") (pinfunction "1_1") (pintype "input"))
      (node (ref "R1") (pin "1") (pinfunction "1_1") (pintype "input"))
      (node (ref "R6") (pin "2") (pinfunction "2_2") (pintype "input"))
      (node (ref "U3") (pin "3") (pinfunction "IN1+_3") (pintype "input"))
    )
    (net (code "37") (name "Net-(U3A-IN1-)") (class "Default")
      (node (ref "R12") (pin "2") (pinfunction "2_2") (pintype "input"))
      (node (ref "R13") (pin "1") (pinfunction "1_1") (pintype "unspecified"))
      (node (ref "R14") (pin "1") (pinfunction "1_1") (pintype "unspecified"))
      (node (ref "R15") (pin "1") (pinfunction "1_1") (pintype "unspecified"))
      (node (ref "R9") (pin "2") (pinfunction "2_2") (pintype "unspecified"))
      (node (ref "U3") (pin "2") (pinfunction "IN1-_2") (pintype "input"))
    )
    (net (code "38") (name "Net-(U3A-OUT)") (class "Default")
      (node (ref "C1") (pin "2") (pinfunction "2_2") (pintype "input"))
      (node (ref "R11") (pin "1") (pinfunction "1_1") (pintype "unspecified"))
      (node (ref "R9") (pin "1") (pinfunction "1_1") (pintype "unspecified"))
      (node (ref "U3") (pin "1") (pinfunction "OUT_1") (pintype "output"))
    )
    (net (code "39") (name "Net-(U3B-IN2+)") (class "Default")
      (node (ref "C15") (pin "1") (pinfunction "1_1") (pintype "unspecified"))
      (node (ref "R12") (pin "1") (pinfunction "1_1") (pintype "input"))
      (node (ref "R13") (pin "2") (pinfunction "2_2") (pintype "unspecified"))
      (node (ref "R14") (pin "2") (pinfunction "2_2") (pintype "unspecified"))
      (node (ref "R15") (pin "2") (pinfunction "2_2") (pintype "unspecified"))
      (node (ref "U3") (pin "5") (pinfunction "IN2+_5") (pintype "input"))
    )
    (net (code "40") (name "Net-(U3B-IN2-)") (class "Default")
      (node (ref "R11") (pin "2") (pinfunction "2_2") (pintype "unspecified"))
      (node (ref "R16") (pin "1") (pinfunction "1_1") (pintype "unspecified"))
      (node (ref "U3") (pin "6") (pinfunction "IN2-_6") (pintype "input"))
    )
    (net (code "41") (name "Net-(U3B-OUT2)") (class "Default")
      (node (ref "C10") (pin "1") (pinfunction "1_1") (pintype "input"))
      (node (ref "C11") (pin "1") (pinfunction "1_1") (pintype "input"))
      (node (ref "C12") (pin "1") (pinfunction "1_1") (pintype "input"))
      (node (ref "C9") (pin "1") (pinfunction "1_1") (pintype "input"))
      (node (ref "H6") (pin "1") (pinfunction "1_1") (pintype "input"))
      (node (ref "L2") (pin "2") (pinfunction "2_2") (pintype "input"))
      (node (ref "R16") (pin "2") (pinfunction "2_2") (pintype "unspecified"))
      (node (ref "U3") (pin "7") (pinfunction "OUT2_7") (pintype "output"))
    )
    (net (code "42") (name "unconnected-(U1-NRST-Pad7)") (class "Default")
      (node (ref "U1") (pin "7") (pinfunction "NRST_7") (pintype "input"))
    )
    (net (code "43") (name "unconnected-(U1-PA2-Pad12)") (class "Default")
      (node (ref "U1") (pin "12") (pinfunction "PA2_12") (pintype "input"))
    )
    (net (code "44") (name "unconnected-(U1-PA3-Pad13)") (class "Default")
      (node (ref "U1") (pin "13") (pinfunction "PA3_13") (pintype "input"))
    )
    (net (code "45") (name "unconnected-(U1-PA4-Pad14)") (class "Default")
      (node (ref "U1") (pin "14") (pinfunction "PA4_14") (pintype "input"))
    )
    (net (code "46") (name "unconnected-(U1-PA5-Pad15)") (class "Default")
      (node (ref "U1") (pin "15") (pinfunction "PA5_15") (pintype "input"))
    )
    (net (code "47") (name "unconnected-(U1-PA6-Pad16)") (class "Default")
      (node (ref "U1") (pin "16") (pinfunction "PA6_16") (pintype "input"))
    )
    (net (code "48") (name "unconnected-(U1-PA7-Pad17)") (class "Default")
      (node (ref "U1") (pin "17") (pinfunction "PA7_17") (pintype "input"))
    )
    (net (code "49") (name "unconnected-(U1-PA8-Pad29)") (class "Default")
      (node (ref "U1") (pin "29") (pinfunction "PA8_29") (pintype "input"))
    )
    (net (code "50") (name "unconnected-(U1-PA10-Pad31)") (class "Default")
      (node (ref "U1") (pin "31") (pinfunction "PA10_31") (pintype "input"))
    )
    (net (code "51") (name "unconnected-(U1-PA11-Pad32)") (class "Default")
      (node (ref "U1") (pin "32") (pinfunction "PA11_32") (pintype "input"))
    )
    (net (code "52") (name "unconnected-(U1-PA12-Pad33)") (class "Default")
      (node (ref "U1") (pin "33") (pinfunction "PA12_33") (pintype "input"))
    )
    (net (code "53") (name "unconnected-(U1-PB0-Pad18)") (class "Default")
      (node (ref "U1") (pin "18") (pinfunction "PB0_18") (pintype "input"))
    )
    (net (code "54") (name "unconnected-(U1-PB1-Pad19)") (class "Default")
      (node (ref "U1") (pin "19") (pinfunction "PB1_19") (pintype "input"))
    )
    (net (code "55") (name "unconnected-(U1-PB2-Pad20)") (class "Default")
      (node (ref "U1") (pin "20") (pinfunction "PB2_20") (pintype "input"))
    )
    (net (code "56") (name "unconnected-(U1-PB8-Pad45)") (class "Default")
      (node (ref "U1") (pin "45") (pinfunction "PB8_45") (pintype "input"))
    )
    (net (code "57") (name "unconnected-(U1-PB9-Pad46)") (class "Default")
      (node (ref "U1") (pin "46") (pinfunction "PB9_46") (pintype "input"))
    )
    (net (code "58") (name "unconnected-(U1-PB10-Pad21)") (class "Default")
      (node (ref "U1") (pin "21") (pinfunction "PB10_21") (pintype "input"))
    )
    (net (code "59") (name "unconnected-(U1-PB11-Pad22)") (class "Default")
      (node (ref "U1") (pin "22") (pinfunction "PB11_22") (pintype "input"))
    )
    (net (code "60") (name "unconnected-(U1-PB12-Pad25)") (class "Default")
      (node (ref "U1") (pin "25") (pinfunction "PB12_25") (pintype "input"))
    )
    (net (code "61") (name "unconnected-(U1-PB13-Pad26)") (class "Default")
      (node (ref "U1") (pin "26") (pinfunction "PB13_26") (pintype "input"))
    )
    (net (code "62") (name "unconnected-(U1-PB14-Pad27)") (class "Default")
      (node (ref "U1") (pin "27") (pinfunction "PB14_27") (pintype "input"))
    )
    (net (code "63") (name "unconnected-(U1-PB15-Pad28)") (class "Default")
      (node (ref "U1") (pin "28") (pinfunction "PB15_28") (pintype "input"))
    )
    (net (code "64") (name "unconnected-(U1-PC13-Pad2)") (class "Default")
      (node (ref "U1") (pin "2") (pinfunction "PC13_2") (pintype "input"))
    )
    (net (code "65") (name "unconnected-(U1-PC14-OSC32_IN-Pad3)") (class "Default")
      (node (ref "U1") (pin "3") (pinfunction "PC14-OSC32_IN_3") (pintype "input"))
    )
    (net (code "66") (name "unconnected-(U1-PC15-OSC32_OUT-Pad4)") (class "Default")
      (node (ref "U1") (pin "4") (pinfunction "PC15-OSC32_OUT_4") (pintype "input"))
    )
    (net (code "67") (name "unconnected-(U1-PF6-Pad35)") (class "Default")
      (node (ref "U1") (pin "35") (pinfunction "PF6_35") (pintype "input"))
    )
    (net (code "68") (name "unconnected-(U1-PF7-Pad36)") (class "Default")
      (node (ref "U1") (pin "36") (pinfunction "PF7_36") (pintype "input"))
    )
  )
)
